# ProtoCard-Prod-V1_0.net
KiCad netlist of a schematic drawn in EAGLE
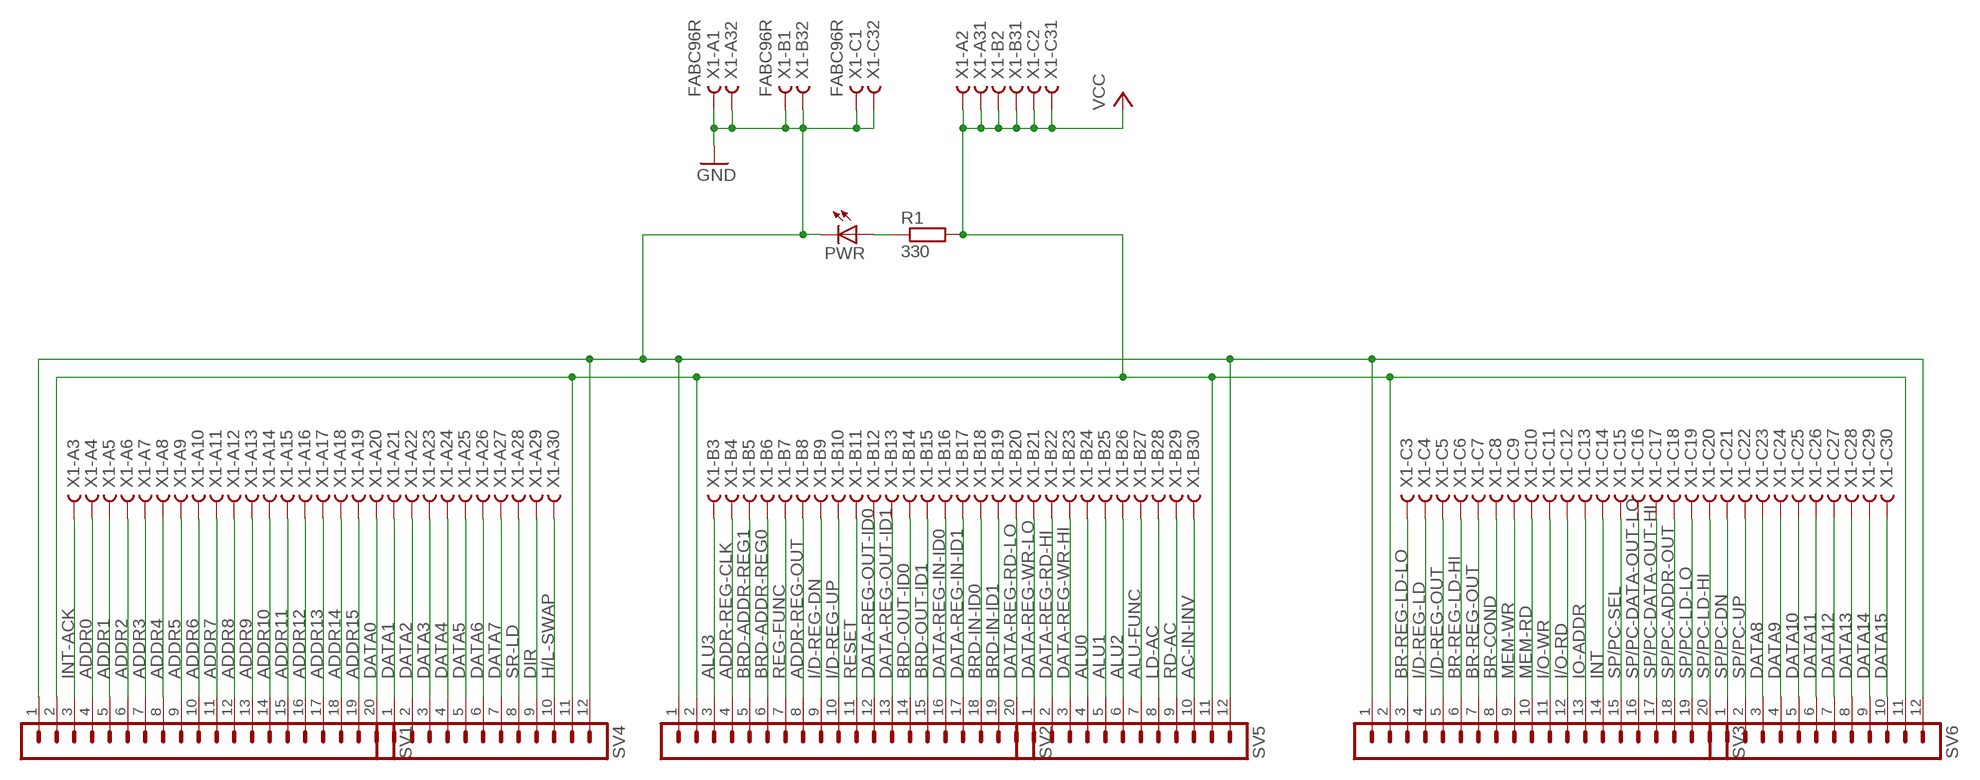
[diagram p0: schematic, sheet 1]

(export (version "E")
  (design (tool "Eeschema 10.0.6"))
  (components
    (comp (ref "PWR")
      (value "LED5MM")
      (footprint "eagle-import:LED5MM")
      (libsource (lib "eagle-import") (part "LED5MM"))
    )
    (comp (ref "R1")
      (value "330")
      (footprint "eagle-import:0207_10")
      (libsource (lib "eagle-import") (part "R0207/10"))
    )
    (comp (ref "SV1")
      (value "MA20-1")
      (footprint "eagle-import:MA20-1")
      (libsource (lib "eagle-import") (part "MA20-1"))
    )
    (comp (ref "SV2")
      (value "MA20-1")
      (footprint "eagle-import:MA20-1")
      (libsource (lib "eagle-import") (part "MA20-1"))
    )
    (comp (ref "SV3")
      (value "MA20-1")
      (footprint "eagle-import:MA20-1")
      (libsource (lib "eagle-import") (part "MA20-1"))
    )
    (comp (ref "SV4")
      (value "MA12-1")
      (footprint "eagle-import:MA12-1")
      (libsource (lib "eagle-import") (part "MA12-1"))
    )
    (comp (ref "SV5")
      (value "MA12-1")
      (footprint "eagle-import:MA12-1")
      (libsource (lib "eagle-import") (part "MA12-1"))
    )
    (comp (ref "SV6")
      (value "MA12-1")
      (footprint "eagle-import:MA12-1")
      (libsource (lib "eagle-import") (part "MA12-1"))
    )
    (comp (ref "X1")
      (value "FABC96R")
      (footprint "eagle-import:FABC96R")
      (libsource (lib "eagle-import") (part "FABC96R"))
    )
  )
  (nets
    (net (code "1") (name "/AC-IN-INV") (class "Default")
      (node (ref "SV5") (pin "10") (pinfunction "10_10") (pintype "passive"))
      (node (ref "X1") (pin "B30") (pinfunction "B_B30") (pintype "passive"))
    )
    (net (code "2") (name "/ADDR-REG-CLK") (class "Default")
      (node (ref "SV2") (pin "4") (pinfunction "4_4") (pintype "passive"))
      (node (ref "X1") (pin "B4") (pinfunction "B_B4") (pintype "passive"))
    )
    (net (code "3") (name "/ADDR-REG-OUT") (class "Default")
      (node (ref "SV2") (pin "8") (pinfunction "8_8") (pintype "passive"))
      (node (ref "X1") (pin "B8") (pinfunction "B_B8") (pintype "passive"))
    )
    (net (code "4") (name "/ADDR0") (class "Default")
      (node (ref "SV1") (pin "4") (pinfunction "4_4") (pintype "passive"))
      (node (ref "X1") (pin "A4") (pinfunction "B_A4") (pintype "passive"))
    )
    (net (code "5") (name "/ADDR1") (class "Default")
      (node (ref "SV1") (pin "5") (pinfunction "5_5") (pintype "passive"))
      (node (ref "X1") (pin "A5") (pinfunction "B_A5") (pintype "passive"))
    )
    (net (code "6") (name "/ADDR2") (class "Default")
      (node (ref "SV1") (pin "6") (pinfunction "6_6") (pintype "passive"))
      (node (ref "X1") (pin "A6") (pinfunction "B_A6") (pintype "passive"))
    )
    (net (code "7") (name "/ADDR3") (class "Default")
      (node (ref "SV1") (pin "7") (pinfunction "7_7") (pintype "passive"))
      (node (ref "X1") (pin "A7") (pinfunction "B_A7") (pintype "passive"))
    )
    (net (code "8") (name "/ADDR4") (class "Default")
      (node (ref "SV1") (pin "8") (pinfunction "8_8") (pintype "passive"))
      (node (ref "X1") (pin "A8") (pinfunction "B_A8") (pintype "passive"))
    )
    (net (code "9") (name "/ADDR5") (class "Default")
      (node (ref "SV1") (pin "9") (pinfunction "9_9") (pintype "passive"))
      (node (ref "X1") (pin "A9") (pinfunction "B_A9") (pintype "passive"))
    )
    (net (code "10") (name "/ADDR6") (class "Default")
      (node (ref "SV1") (pin "10") (pinfunction "10_10") (pintype "passive"))
      (node (ref "X1") (pin "A10") (pinfunction "B_A10") (pintype "passive"))
    )
    (net (code "11") (name "/ADDR7") (class "Default")
      (node (ref "SV1") (pin "11") (pinfunction "11_11") (pintype "passive"))
      (node (ref "X1") (pin "A11") (pinfunction "B_A11") (pintype "passive"))
    )
    (net (code "12") (name "/ADDR8") (class "Default")
      (node (ref "SV1") (pin "12") (pinfunction "12_12") (pintype "passive"))
      (node (ref "X1") (pin "A12") (pinfunction "B_A12") (pintype "passive"))
    )
    (net (code "13") (name "/ADDR9") (class "Default")
      (node (ref "SV1") (pin "13") (pinfunction "13_13") (pintype "passive"))
      (node (ref "X1") (pin "A13") (pinfunction "B_A13") (pintype "passive"))
    )
    (net (code "14") (name "/ADDR10") (class "Default")
      (node (ref "SV1") (pin "14") (pinfunction "14_14") (pintype "passive"))
      (node (ref "X1") (pin "A14") (pinfunction "B_A14") (pintype "passive"))
    )
    (net (code "15") (name "/ADDR11") (class "Default")
      (node (ref "SV1") (pin "15") (pinfunction "15_15") (pintype "passive"))
      (node (ref "X1") (pin "A15") (pinfunction "B_A15") (pintype "passive"))
    )
    (net (code "16") (name "/ADDR12") (class "Default")
      (node (ref "SV1") (pin "16") (pinfunction "16_16") (pintype "passive"))
      (node (ref "X1") (pin "A16") (pinfunction "B_A16") (pintype "passive"))
    )
    (net (code "17") (name "/ADDR13") (class "Default")
      (node (ref "SV1") (pin "17") (pinfunction "17_17") (pintype "passive"))
      (node (ref "X1") (pin "A17") (pinfunction "B_A17") (pintype "passive"))
    )
    (net (code "18") (name "/ADDR14") (class "Default")
      (node (ref "SV1") (pin "18") (pinfunction "18_18") (pintype "passive"))
      (node (ref "X1") (pin "A18") (pinfunction "B_A18") (pintype "passive"))
    )
    (net (code "19") (name "/ADDR15") (class "Default")
      (node (ref "SV1") (pin "19") (pinfunction "19_19") (pintype "passive"))
      (node (ref "X1") (pin "A19") (pinfunction "B_A19") (pintype "passive"))
    )
    (net (code "20") (name "/ALU-FUNC") (class "Default")
      (node (ref "SV5") (pin "7") (pinfunction "7_7") (pintype "passive"))
      (node (ref "X1") (pin "B27") (pinfunction "B_B27") (pintype "passive"))
    )
    (net (code "21") (name "/ALU0") (class "Default")
      (node (ref "SV5") (pin "4") (pinfunction "4_4") (pintype "passive"))
      (node (ref "X1") (pin "B24") (pinfunction "B_B24") (pintype "passive"))
    )
    (net (code "22") (name "/ALU1") (class "Default")
      (node (ref "SV5") (pin "5") (pinfunction "5_5") (pintype "passive"))
      (node (ref "X1") (pin "B25") (pinfunction "B_B25") (pintype "passive"))
    )
    (net (code "23") (name "/ALU2") (class "Default")
      (node (ref "SV5") (pin "6") (pinfunction "6_6") (pintype "passive"))
      (node (ref "X1") (pin "B26") (pinfunction "B_B26") (pintype "passive"))
    )
    (net (code "24") (name "/ALU3") (class "Default")
      (node (ref "SV2") (pin "3") (pinfunction "3_3") (pintype "passive"))
      (node (ref "X1") (pin "B3") (pinfunction "B_B3") (pintype "passive"))
    )
    (net (code "25") (name "/BR-COND") (class "Default")
      (node (ref "SV3") (pin "8") (pinfunction "8_8") (pintype "passive"))
      (node (ref "X1") (pin "C8") (pinfunction "B_C8") (pintype "passive"))
    )
    (net (code "26") (name "/BR-REG-LD-HI") (class "Default")
      (node (ref "SV3") (pin "6") (pinfunction "6_6") (pintype "passive"))
      (node (ref "X1") (pin "C6") (pinfunction "B_C6") (pintype "passive"))
    )
    (net (code "27") (name "/BR-REG-LD-LO") (class "Default")
      (node (ref "SV3") (pin "3") (pinfunction "3_3") (pintype "passive"))
      (node (ref "X1") (pin "C3") (pinfunction "B_C3") (pintype "passive"))
    )
    (net (code "28") (name "/BR-REG-OUT") (class "Default")
      (node (ref "SV3") (pin "7") (pinfunction "7_7") (pintype "passive"))
      (node (ref "X1") (pin "C7") (pinfunction "B_C7") (pintype "passive"))
    )
    (net (code "29") (name "/BRD-ADDR-REG0") (class "Default")
      (node (ref "SV2") (pin "6") (pinfunction "6_6") (pintype "passive"))
      (node (ref "X1") (pin "B6") (pinfunction "B_B6") (pintype "passive"))
    )
    (net (code "30") (name "/BRD-ADDR-REG1") (class "Default")
      (node (ref "SV2") (pin "5") (pinfunction "5_5") (pintype "passive"))
      (node (ref "X1") (pin "B5") (pinfunction "B_B5") (pintype "passive"))
    )
    (net (code "31") (name "/BRD-IN-ID0") (class "Default")
      (node (ref "SV2") (pin "18") (pinfunction "18_18") (pintype "passive"))
      (node (ref "X1") (pin "B18") (pinfunction "B_B18") (pintype "passive"))
    )
    (net (code "32") (name "/BRD-IN-ID1") (class "Default")
      (node (ref "SV2") (pin "19") (pinfunction "19_19") (pintype "passive"))
      (node (ref "X1") (pin "B19") (pinfunction "B_B19") (pintype "passive"))
    )
    (net (code "33") (name "/BRD-OUT-ID0") (class "Default")
      (node (ref "SV2") (pin "14") (pinfunction "14_14") (pintype "passive"))
      (node (ref "X1") (pin "B14") (pinfunction "B_B14") (pintype "passive"))
    )
    (net (code "34") (name "/BRD-OUT-ID1") (class "Default")
      (node (ref "SV2") (pin "15") (pinfunction "15_15") (pintype "passive"))
      (node (ref "X1") (pin "B15") (pinfunction "B_B15") (pintype "passive"))
    )
    (net (code "35") (name "/DATA-REG-IN-ID0") (class "Default")
      (node (ref "SV2") (pin "16") (pinfunction "16_16") (pintype "passive"))
      (node (ref "X1") (pin "B16") (pinfunction "B_B16") (pintype "passive"))
    )
    (net (code "36") (name "/DATA-REG-IN-ID1") (class "Default")
      (node (ref "SV2") (pin "17") (pinfunction "17_17") (pintype "passive"))
      (node (ref "X1") (pin "B17") (pinfunction "B_B17") (pintype "passive"))
    )
    (net (code "37") (name "/DATA-REG-OUT-ID0") (class "Default")
      (node (ref "SV2") (pin "12") (pinfunction "12_12") (pintype "passive"))
      (node (ref "X1") (pin "B12") (pinfunction "B_B12") (pintype "passive"))
    )
    (net (code "38") (name "/DATA-REG-OUT-ID1") (class "Default")
      (node (ref "SV2") (pin "13") (pinfunction "13_13") (pintype "passive"))
      (node (ref "X1") (pin "B13") (pinfunction "B_B13") (pintype "passive"))
    )
    (net (code "39") (name "/DATA-REG-RD-HI") (class "Default")
      (node (ref "SV5") (pin "2") (pinfunction "2_2") (pintype "passive"))
      (node (ref "X1") (pin "B22") (pinfunction "B_B22") (pintype "passive"))
    )
    (net (code "40") (name "/DATA-REG-RD-LO") (class "Default")
      (node (ref "SV2") (pin "20") (pinfunction "20_20") (pintype "passive"))
      (node (ref "X1") (pin "B20") (pinfunction "B_B20") (pintype "passive"))
    )
    (net (code "41") (name "/DATA-REG-WR-HI") (class "Default")
      (node (ref "SV5") (pin "3") (pinfunction "3_3") (pintype "passive"))
      (node (ref "X1") (pin "B23") (pinfunction "B_B23") (pintype "passive"))
    )
    (net (code "42") (name "/DATA-REG-WR-LO") (class "Default")
      (node (ref "SV5") (pin "1") (pinfunction "1_1") (pintype "passive"))
      (node (ref "X1") (pin "B21") (pinfunction "B_B21") (pintype "passive"))
    )
    (net (code "43") (name "/DATA0") (class "Default")
      (node (ref "SV1") (pin "20") (pinfunction "20_20") (pintype "passive"))
      (node (ref "X1") (pin "A20") (pinfunction "B_A20") (pintype "passive"))
    )
    (net (code "44") (name "/DATA1") (class "Default")
      (node (ref "SV4") (pin "1") (pinfunction "1_1") (pintype "passive"))
      (node (ref "X1") (pin "A21") (pinfunction "B_A21") (pintype "passive"))
    )
    (net (code "45") (name "/DATA2") (class "Default")
      (node (ref "SV4") (pin "2") (pinfunction "2_2") (pintype "passive"))
      (node (ref "X1") (pin "A22") (pinfunction "B_A22") (pintype "passive"))
    )
    (net (code "46") (name "/DATA3") (class "Default")
      (node (ref "SV4") (pin "3") (pinfunction "3_3") (pintype "passive"))
      (node (ref "X1") (pin "A23") (pinfunction "B_A23") (pintype "passive"))
    )
    (net (code "47") (name "/DATA4") (class "Default")
      (node (ref "SV4") (pin "4") (pinfunction "4_4") (pintype "passive"))
      (node (ref "X1") (pin "A24") (pinfunction "B_A24") (pintype "passive"))
    )
    (net (code "48") (name "/DATA5") (class "Default")
      (node (ref "SV4") (pin "5") (pinfunction "5_5") (pintype "passive"))
      (node (ref "X1") (pin "A25") (pinfunction "B_A25") (pintype "passive"))
    )
    (net (code "49") (name "/DATA6") (class "Default")
      (node (ref "SV4") (pin "6") (pinfunction "6_6") (pintype "passive"))
      (node (ref "X1") (pin "A26") (pinfunction "B_A26") (pintype "passive"))
    )
    (net (code "50") (name "/DATA7") (class "Default")
      (node (ref "SV4") (pin "7") (pinfunction "7_7") (pintype "passive"))
      (node (ref "X1") (pin "A27") (pinfunction "B_A27") (pintype "passive"))
    )
    (net (code "51") (name "/DATA8") (class "Default")
      (node (ref "SV6") (pin "3") (pinfunction "3_3") (pintype "passive"))
      (node (ref "X1") (pin "C23") (pinfunction "B_C23") (pintype "passive"))
    )
    (net (code "52") (name "/DATA9") (class "Default")
      (node (ref "SV6") (pin "4") (pinfunction "4_4") (pintype "passive"))
      (node (ref "X1") (pin "C24") (pinfunction "B_C24") (pintype "passive"))
    )
    (net (code "53") (name "/DATA10") (class "Default")
      (node (ref "SV6") (pin "5") (pinfunction "5_5") (pintype "passive"))
      (node (ref "X1") (pin "C25") (pinfunction "B_C25") (pintype "passive"))
    )
    (net (code "54") (name "/DATA11") (class "Default")
      (node (ref "SV6") (pin "6") (pinfunction "6_6") (pintype "passive"))
      (node (ref "X1") (pin "C26") (pinfunction "B_C26") (pintype "passive"))
    )
    (net (code "55") (name "/DATA12") (class "Default")
      (node (ref "SV6") (pin "7") (pinfunction "7_7") (pintype "passive"))
      (node (ref "X1") (pin "C27") (pinfunction "B_C27") (pintype "passive"))
    )
    (net (code "56") (name "/DATA13") (class "Default")
      (node (ref "SV6") (pin "8") (pinfunction "8_8") (pintype "passive"))
      (node (ref "X1") (pin "C28") (pinfunction "B_C28") (pintype "passive"))
    )
    (net (code "57") (name "/DATA14") (class "Default")
      (node (ref "SV6") (pin "9") (pinfunction "9_9") (pintype "passive"))
      (node (ref "X1") (pin "C29") (pinfunction "B_C29") (pintype "passive"))
    )
    (net (code "58") (name "/DATA15") (class "Default")
      (node (ref "SV6") (pin "10") (pinfunction "10_10") (pintype "passive"))
      (node (ref "X1") (pin "C30") (pinfunction "B_C30") (pintype "passive"))
    )
    (net (code "59") (name "/DIR") (class "Default")
      (node (ref "SV4") (pin "9") (pinfunction "9_9") (pintype "passive"))
      (node (ref "X1") (pin "A29") (pinfunction "B_A29") (pintype "passive"))
    )
    (net (code "60") (name "/H{slash}L-SWAP") (class "Default")
      (node (ref "SV4") (pin "10") (pinfunction "10_10") (pintype "passive"))
      (node (ref "X1") (pin "A30") (pinfunction "B_A30") (pintype "passive"))
    )
    (net (code "61") (name "/INT") (class "Default")
      (node (ref "SV3") (pin "14") (pinfunction "14_14") (pintype "passive"))
      (node (ref "X1") (pin "C14") (pinfunction "B_C14") (pintype "passive"))
    )
    (net (code "62") (name "/INT-ACK") (class "Default")
      (node (ref "SV1") (pin "3") (pinfunction "3_3") (pintype "passive"))
      (node (ref "X1") (pin "A3") (pinfunction "B_A3") (pintype "passive"))
    )
    (net (code "63") (name "/IO-ADDR") (class "Default")
      (node (ref "SV3") (pin "13") (pinfunction "13_13") (pintype "passive"))
      (node (ref "X1") (pin "C13") (pinfunction "B_C13") (pintype "passive"))
    )
    (net (code "64") (name "/I{slash}D-REG-DN") (class "Default")
      (node (ref "SV2") (pin "9") (pinfunction "9_9") (pintype "passive"))
      (node (ref "X1") (pin "B9") (pinfunction "B_B9") (pintype "passive"))
    )
    (net (code "65") (name "/I{slash}D-REG-LD") (class "Default")
      (node (ref "SV3") (pin "4") (pinfunction "4_4") (pintype "passive"))
      (node (ref "X1") (pin "C4") (pinfunction "B_C4") (pintype "passive"))
    )
    (net (code "66") (name "/I{slash}D-REG-OUT") (class "Default")
      (node (ref "SV3") (pin "5") (pinfunction "5_5") (pintype "passive"))
      (node (ref "X1") (pin "C5") (pinfunction "B_C5") (pintype "passive"))
    )
    (net (code "67") (name "/I{slash}D-REG-UP") (class "Default")
      (node (ref "SV2") (pin "10") (pinfunction "10_10") (pintype "passive"))
      (node (ref "X1") (pin "B10") (pinfunction "B_B10") (pintype "passive"))
    )
    (net (code "68") (name "/I{slash}O-RD") (class "Default")
      (node (ref "SV3") (pin "12") (pinfunction "12_12") (pintype "passive"))
      (node (ref "X1") (pin "C12") (pinfunction "B_C12") (pintype "passive"))
    )
    (net (code "69") (name "/I{slash}O-WR") (class "Default")
      (node (ref "SV3") (pin "11") (pinfunction "11_11") (pintype "passive"))
      (node (ref "X1") (pin "C11") (pinfunction "B_C11") (pintype "passive"))
    )
    (net (code "70") (name "/LD-AC") (class "Default")
      (node (ref "SV5") (pin "8") (pinfunction "8_8") (pintype "passive"))
      (node (ref "X1") (pin "B28") (pinfunction "B_B28") (pintype "passive"))
    )
    (net (code "71") (name "/MEM-RD") (class "Default")
      (node (ref "SV3") (pin "10") (pinfunction "10_10") (pintype "passive"))
      (node (ref "X1") (pin "C10") (pinfunction "B_C10") (pintype "passive"))
    )
    (net (code "72") (name "/MEM-WR") (class "Default")
      (node (ref "SV3") (pin "9") (pinfunction "9_9") (pintype "passive"))
      (node (ref "X1") (pin "C9") (pinfunction "B_C9") (pintype "passive"))
    )
    (net (code "73") (name "/RD-AC") (class "Default")
      (node (ref "SV5") (pin "9") (pinfunction "9_9") (pintype "passive"))
      (node (ref "X1") (pin "B29") (pinfunction "B_B29") (pintype "passive"))
    )
    (net (code "74") (name "/REG-FUNC") (class "Default")
      (node (ref "SV2") (pin "7") (pinfunction "7_7") (pintype "passive"))
      (node (ref "X1") (pin "B7") (pinfunction "B_B7") (pintype "passive"))
    )
    (net (code "75") (name "/RESET") (class "Default")
      (node (ref "SV2") (pin "11") (pinfunction "11_11") (pintype "passive"))
      (node (ref "X1") (pin "B11") (pinfunction "B_B11") (pintype "passive"))
    )
    (net (code "76") (name "/SP{slash}PC-ADDR-OUT") (class "Default")
      (node (ref "SV3") (pin "18") (pinfunction "18_18") (pintype "passive"))
      (node (ref "X1") (pin "C18") (pinfunction "B_C18") (pintype "passive"))
    )
    (net (code "77") (name "/SP{slash}PC-DATA-OUT-HI") (class "Default")
      (node (ref "SV3") (pin "17") (pinfunction "17_17") (pintype "passive"))
      (node (ref "X1") (pin "C17") (pinfunction "B_C17") (pintype "passive"))
    )
    (net (code "78") (name "/SP{slash}PC-DATA-OUT-LO") (class "Default")
      (node (ref "SV3") (pin "16") (pinfunction "16_16") (pintype "passive"))
      (node (ref "X1") (pin "C16") (pinfunction "B_C16") (pintype "passive"))
    )
    (net (code "79") (name "/SP{slash}PC-DN") (class "Default")
      (node (ref "SV6") (pin "1") (pinfunction "1_1") (pintype "passive"))
      (node (ref "X1") (pin "C21") (pinfunction "B_C21") (pintype "passive"))
    )
    (net (code "80") (name "/SP{slash}PC-LD-HI") (class "Default")
      (node (ref "SV3") (pin "20") (pinfunction "20_20") (pintype "passive"))
      (node (ref "X1") (pin "C20") (pinfunction "B_C20") (pintype "passive"))
    )
    (net (code "81") (name "/SP{slash}PC-LD-LO") (class "Default")
      (node (ref "SV3") (pin "19") (pinfunction "19_19") (pintype "passive"))
      (node (ref "X1") (pin "C19") (pinfunction "B_C19") (pintype "passive"))
    )
    (net (code "82") (name "/SP{slash}PC-SEL") (class "Default")
      (node (ref "SV3") (pin "15") (pinfunction "15_15") (pintype "passive"))
      (node (ref "X1") (pin "C15") (pinfunction "B_C15") (pintype "passive"))
    )
    (net (code "83") (name "/SP{slash}PC-UP") (class "Default")
      (node (ref "SV6") (pin "2") (pinfunction "2_2") (pintype "passive"))
      (node (ref "X1") (pin "C22") (pinfunction "B_C22") (pintype "passive"))
    )
    (net (code "84") (name "/SR-LD") (class "Default")
      (node (ref "SV4") (pin "8") (pinfunction "8_8") (pintype "passive"))
      (node (ref "X1") (pin "A28") (pinfunction "B_A28") (pintype "passive"))
    )
    (net (code "85") (name "GND") (class "Default")
      (node (ref "PWR") (pin "K") (pinfunction "C_K") (pintype "passive"))
      (node (ref "SV1") (pin "1") (pinfunction "1_1") (pintype "passive"))
      (node (ref "SV2") (pin "1") (pinfunction "1_1") (pintype "passive"))
      (node (ref "SV3") (pin "1") (pinfunction "1_1") (pintype "passive"))
      (node (ref "SV4") (pin "12") (pinfunction "12_12") (pintype "passive"))
      (node (ref "SV5") (pin "12") (pinfunction "12_12") (pintype "passive"))
      (node (ref "SV6") (pin "12") (pinfunction "12_12") (pintype "passive"))
      (node (ref "X1") (pin "A1") (pinfunction "B_A1") (pintype "passive"))
      (node (ref "X1") (pin "A32") (pinfunction "B_A32") (pintype "passive"))
      (node (ref "X1") (pin "B1") (pinfunction "B_B1") (pintype "passive"))
      (node (ref "X1") (pin "B32") (pinfunction "B_B32") (pintype "passive"))
      (node (ref "X1") (pin "C1") (pinfunction "B_C1") (pintype "passive"))
      (node (ref "X1") (pin "C32") (pinfunction "B_C32") (pintype "passive"))
    )
    (net (code "86") (name "Net-(PWR-PadA)") (class "Default")
      (node (ref "PWR") (pin "A") (pinfunction "A_A") (pintype "passive"))
      (node (ref "R1") (pin "1") (pinfunction "1_1") (pintype "passive"))
    )
    (net (code "87") (name "VCC") (class "Default")
      (node (ref "R1") (pin "2") (pinfunction "2_2") (pintype "passive"))
      (node (ref "SV1") (pin "2") (pinfunction "2_2") (pintype "passive"))
      (node (ref "SV2") (pin "2") (pinfunction "2_2") (pintype "passive"))
      (node (ref "SV3") (pin "2") (pinfunction "2_2") (pintype "passive"))
      (node (ref "SV4") (pin "11") (pinfunction "11_11") (pintype "passive"))
      (node (ref "SV5") (pin "11") (pinfunction "11_11") (pintype "passive"))
      (node (ref "SV6") (pin "11") (pinfunction "11_11") (pintype "passive"))
      (node (ref "X1") (pin "A2") (pinfunction "B_A2") (pintype "passive"))
      (node (ref "X1") (pin "A31") (pinfunction "B_A31") (pintype "passive"))
      (node (ref "X1") (pin "B2") (pinfunction "B_B2") (pintype "passive"))
      (node (ref "X1") (pin "B31") (pinfunction "B_B31") (pintype "passive"))
      (node (ref "X1") (pin "C2") (pinfunction "B_C2") (pintype "passive"))
      (node (ref "X1") (pin "C31") (pinfunction "B_C31") (pintype "passive"))
    )
  )
)
